# Cutman-RevB.net
KiCad netlist of a schematic drawn in EAGLE
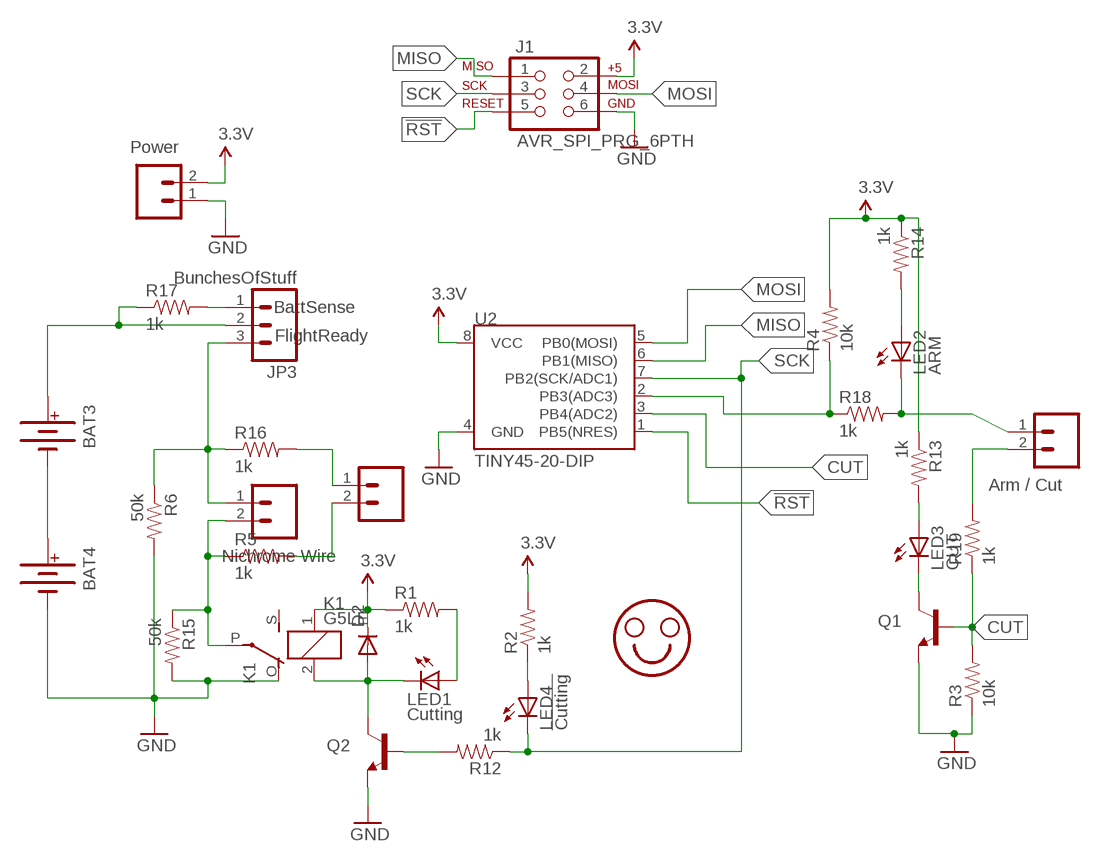
[diagram p0: schematic, sheet 1]

(export (version "E")
  (design (tool "Eeschema 10.0.6"))
  (components
    (comp (ref "BAT3")
      (value "BATTERYAA-KIT")
      (footprint "eagle-import:BATTERY-AA-KIT")
      (libsource (lib "eagle-import") (part "BATTERYAA-KIT"))
    )
    (comp (ref "BAT4")
      (value "BATTERYAA-KIT")
      (footprint "eagle-import:BATTERY-AA-KIT")
      (libsource (lib "eagle-import") (part "BATTERYAA-KIT"))
    )
    (comp (ref "D2")
      (value "DIODEPTH")
      (footprint "eagle-import:DIODE-1N4001")
      (libsource (lib "eagle-import") (part "DIODEPTH"))
    )
    (comp (ref "J1")
      (value "AVR_SPI_PRG_6PTH")
      (footprint "eagle-import:2X3")
      (libsource (lib "eagle-import") (part "AVR_SPI_PRG_6PTH"))
    )
    (comp (ref "JP1")
      (value "NichromeWire")
      (footprint "eagle-import:SCREWTERMINAL-3.5MM-2_LOCK")
      (libsource (lib "eagle-import") (part "M023.5MM_LOCK"))
    )
    (comp (ref "JP2")
      (value "Power")
      (footprint "eagle-import:SCREWTERMINAL-3.5MM-2_LOCK")
      (libsource (lib "eagle-import") (part "M023.5MM_LOCK"))
    )
    (comp (ref "JP3")
      (value "BunchesOfStuff")
      (footprint "eagle-import:SCREWTERMINAL-3.5MM-3")
      (libsource (lib "eagle-import") (part "M03SCREW"))
    )
    (comp (ref "JP4")
      (value "VSense")
      (footprint "eagle-import:SCREWTERMINAL-3.5MM-2_LOCK")
      (libsource (lib "eagle-import") (part "M023.5MM_LOCK"))
    )
    (comp (ref "JP6")
      (value "Arm/Cut")
      (footprint "eagle-import:SCREWTERMINAL-3.5MM-2_LOCK")
      (libsource (lib "eagle-import") (part "M023.5MM_LOCK"))
    )
    (comp (ref "K1")
      (value "G5LE")
      (footprint "eagle-import:G5LE")
      (libsource (lib "eagle-import") (part "G5LE"))
    )
    (comp (ref "LED1")
      (value "Cutting")
      (footprint "eagle-import:LED5MM")
      (libsource (lib "eagle-import") (part "LED5MM"))
    )
    (comp (ref "LED2")
      (value "ARM")
      (footprint "eagle-import:LED5MM")
      (libsource (lib "eagle-import") (part "LED5MM"))
    )
    (comp (ref "LED3")
      (value "CUT")
      (footprint "eagle-import:LED5MM")
      (libsource (lib "eagle-import") (part "LED5MM"))
    )
    (comp (ref "LED4")
      (value "!Cutting")
      (footprint "eagle-import:LED5MM")
      (libsource (lib "eagle-import") (part "LED5MM"))
    )
    (comp (ref "Q1")
      (value "TRANSISTOR_NPNTO92")
      (footprint "eagle-import:TO-92")
      (libsource (lib "eagle-import") (part "TRANSISTOR_NPNTO92"))
    )
    (comp (ref "Q2")
      (value "TRANSISTOR_NPNTO92")
      (footprint "eagle-import:TO-92")
      (libsource (lib "eagle-import") (part "TRANSISTOR_NPNTO92"))
    )
    (comp (ref "R1")
      (value "1k")
      (footprint "eagle-import:AXIAL-0.3")
      (libsource (lib "eagle-import") (part "RESISTORAXIAL-0.3"))
    )
    (comp (ref "R2")
      (value "1k")
      (footprint "eagle-import:AXIAL-0.3")
      (libsource (lib "eagle-import") (part "RESISTORAXIAL-0.3"))
    )
    (comp (ref "R3")
      (value "10k")
      (footprint "eagle-import:AXIAL-0.3")
      (libsource (lib "eagle-import") (part "RESISTORAXIAL-0.3"))
    )
    (comp (ref "R4")
      (value "10k")
      (footprint "eagle-import:AXIAL-0.3")
      (libsource (lib "eagle-import") (part "RESISTORAXIAL-0.3"))
    )
    (comp (ref "R5")
      (value "1k")
      (footprint "eagle-import:AXIAL-0.3")
      (libsource (lib "eagle-import") (part "RESISTORAXIAL-0.3"))
    )
    (comp (ref "R6")
      (value "50k")
      (footprint "eagle-import:AXIAL-0.3")
      (libsource (lib "eagle-import") (part "RESISTORAXIAL-0.3"))
    )
    (comp (ref "R12")
      (value "1k")
      (footprint "eagle-import:AXIAL-0.3")
      (libsource (lib "eagle-import") (part "RESISTORAXIAL-0.3"))
    )
    (comp (ref "R13")
      (value "1k")
      (footprint "eagle-import:AXIAL-0.3")
      (libsource (lib "eagle-import") (part "RESISTORAXIAL-0.3"))
    )
    (comp (ref "R14")
      (value "1k")
      (footprint "eagle-import:AXIAL-0.3")
      (libsource (lib "eagle-import") (part "RESISTORAXIAL-0.3"))
    )
    (comp (ref "R15")
      (value "50k")
      (footprint "eagle-import:AXIAL-0.3")
      (libsource (lib "eagle-import") (part "RESISTORAXIAL-0.3"))
    )
    (comp (ref "R16")
      (value "1k")
      (footprint "eagle-import:AXIAL-0.3")
      (libsource (lib "eagle-import") (part "RESISTORAXIAL-0.3"))
    )
    (comp (ref "R17")
      (value "1k")
      (footprint "eagle-import:AXIAL-0.3")
      (libsource (lib "eagle-import") (part "RESISTORAXIAL-0.3"))
    )
    (comp (ref "R18")
      (value "1k")
      (footprint "eagle-import:AXIAL-0.3")
      (libsource (lib "eagle-import") (part "RESISTORAXIAL-0.3"))
    )
    (comp (ref "R19")
      (value "1k")
      (footprint "eagle-import:AXIAL-0.3")
      (libsource (lib "eagle-import") (part "RESISTORAXIAL-0.3"))
    )
    (comp (ref "STANDOFF2")
      (value "STAND-OFF")
      (footprint "eagle-import:STAND-OFF")
      (libsource (lib "eagle-import") (part "STAND-OFF"))
    )
    (comp (ref "STANDOFF3")
      (value "STAND-OFF")
      (footprint "eagle-import:STAND-OFF")
      (libsource (lib "eagle-import") (part "STAND-OFF"))
    )
    (comp (ref "U2")
      (value "TINY45-20-DIP")
      (footprint "eagle-import:DIP08")
      (libsource (lib "eagle-import") (part "ATTINY45TINY45-20-DIP"))
    )
  )
  (nets
    (net (code "1") (name "/~{RST}") (class "Default")
      (node (ref "J1") (pin "5") (pinfunction "5_5") (pintype "passive"))
      (node (ref "U2") (pin "1") (pinfunction "PB5(NRES)_1") (pintype "bidirectional"))
    )
    (net (code "2") (name "3.3V") (class "Default")
      (node (ref "D2") (pin "C") (pinfunction "C_C") (pintype "passive"))
      (node (ref "J1") (pin "2") (pinfunction "2_2") (pintype "passive"))
      (node (ref "JP2") (pin "2") (pinfunction "2_2") (pintype "passive"))
      (node (ref "K1") (pin "1") (pinfunction "1_1") (pintype "passive"))
      (node (ref "R1") (pin "P$1") (pinfunction "1_P$1") (pintype "passive"))
      (node (ref "R13") (pin "P$1") (pinfunction "1_P$1") (pintype "passive"))
      (node (ref "R14") (pin "P$1") (pinfunction "1_P$1") (pintype "passive"))
      (node (ref "R2") (pin "P$2") (pinfunction "2_P$2") (pintype "passive"))
      (node (ref "R4") (pin "P$2") (pinfunction "2_P$2") (pintype "passive"))
      (node (ref "U2") (pin "8") (pinfunction "VCC_8") (pintype "bidirectional"))
    )
    (net (code "3") (name "CUT") (class "Default")
      (node (ref "Q1") (pin "2") (pinfunction "B_2") (pintype "passive"))
      (node (ref "R19") (pin "P$1") (pinfunction "1_P$1") (pintype "passive"))
      (node (ref "R3") (pin "P$2") (pinfunction "2_P$2") (pintype "passive"))
      (node (ref "U2") (pin "3") (pinfunction "PB4(ADC2)_3") (pintype "bidirectional"))
    )
    (net (code "4") (name "GND") (class "Default")
      (node (ref "BAT4") (pin "GND@1") (pinfunction "-_GND@1") (pintype "power_in"))
      (node (ref "BAT4") (pin "GND@2") (pinfunction "-_GND@2") (pintype "power_in"))
      (node (ref "J1") (pin "6") (pinfunction "6_6") (pintype "passive"))
      (node (ref "JP2") (pin "1") (pinfunction "1_1") (pintype "passive"))
      (node (ref "K1") (pin "O") (pinfunction "O_O") (pintype "passive"))
      (node (ref "Q1") (pin "1") (pinfunction "E_1") (pintype "passive"))
      (node (ref "Q2") (pin "1") (pinfunction "E_1") (pintype "passive"))
      (node (ref "R15") (pin "P$2") (pinfunction "2_P$2") (pintype "passive"))
      (node (ref "R3") (pin "P$1") (pinfunction "1_P$1") (pintype "passive"))
      (node (ref "R6") (pin "P$2") (pinfunction "2_P$2") (pintype "passive"))
      (node (ref "U2") (pin "4") (pinfunction "GND_4") (pintype "bidirectional"))
    )
    (net (code "5") (name "MISO") (class "Default")
      (node (ref "J1") (pin "1") (pinfunction "1_1") (pintype "passive"))
      (node (ref "U2") (pin "6") (pinfunction "PB1(MISO)_6") (pintype "bidirectional"))
    )
    (net (code "6") (name "MOSI") (class "Default")
      (node (ref "J1") (pin "4") (pinfunction "4_4") (pintype "passive"))
      (node (ref "U2") (pin "5") (pinfunction "PB0(MOSI)_5") (pintype "bidirectional"))
    )
    (net (code "7") (name "Net-(BAT3---PadGND@1)") (class "Default")
      (node (ref "BAT3") (pin "GND@1") (pinfunction "-_GND@1") (pintype "power_in"))
      (node (ref "BAT3") (pin "GND@2") (pinfunction "-_GND@2") (pintype "power_in"))
      (node (ref "BAT4") (pin "PWR@1") (pinfunction "+_PWR@1") (pintype "power_in"))
      (node (ref "BAT4") (pin "PWR@2") (pinfunction "+_PWR@2") (pintype "power_in"))
    )
    (net (code "8") (name "Net-(LED1-C)") (class "Default")
      (node (ref "D2") (pin "A") (pinfunction "A_A") (pintype "passive"))
      (node (ref "K1") (pin "2") (pinfunction "2_2") (pintype "passive"))
      (node (ref "LED1") (pin "K") (pinfunction "C_K") (pintype "passive"))
      (node (ref "Q2") (pin "3") (pinfunction "C_3") (pintype "passive"))
    )
    (net (code "9") (name "Net-(LED2-C)") (class "Default")
      (node (ref "JP6") (pin "1") (pinfunction "1_1") (pintype "passive"))
      (node (ref "LED2") (pin "K") (pinfunction "C_K") (pintype "passive"))
      (node (ref "R18") (pin "P$2") (pinfunction "2_P$2") (pintype "passive"))
    )
    (net (code "10") (name "Net-(LED3-C)") (class "Default")
      (node (ref "LED3") (pin "K") (pinfunction "C_K") (pintype "passive"))
      (node (ref "Q1") (pin "3") (pinfunction "C_3") (pintype "passive"))
    )
    (net (code "11") (name "Net-(Q2-B)") (class "Default")
      (node (ref "Q2") (pin "2") (pinfunction "B_2") (pintype "passive"))
      (node (ref "R12") (pin "P$2") (pinfunction "2_P$2") (pintype "passive"))
    )
    (net (code "12") (name "Net-(R1-2)") (class "Default")
      (node (ref "LED1") (pin "A") (pinfunction "A_A") (pintype "passive"))
      (node (ref "R1") (pin "P$2") (pinfunction "2_P$2") (pintype "passive"))
    )
    (net (code "13") (name "Net-(R2-1)") (class "Default")
      (node (ref "LED4") (pin "A") (pinfunction "A_A") (pintype "passive"))
      (node (ref "R2") (pin "P$1") (pinfunction "1_P$1") (pintype "passive"))
    )
    (net (code "14") (name "Net-(R5-2)") (class "Default")
      (node (ref "JP4") (pin "2") (pinfunction "2_2") (pintype "passive"))
      (node (ref "R5") (pin "P$2") (pinfunction "2_P$2") (pintype "passive"))
    )
    (net (code "15") (name "Net-(R13-2)") (class "Default")
      (node (ref "LED3") (pin "A") (pinfunction "A_A") (pintype "passive"))
      (node (ref "R13") (pin "P$2") (pinfunction "2_P$2") (pintype "passive"))
    )
    (net (code "16") (name "Net-(R14-2)") (class "Default")
      (node (ref "LED2") (pin "A") (pinfunction "A_A") (pintype "passive"))
      (node (ref "R14") (pin "P$2") (pinfunction "2_P$2") (pintype "passive"))
    )
    (net (code "17") (name "Net-(R15-1)") (class "Default")
      (node (ref "JP1") (pin "2") (pinfunction "2_2") (pintype "passive"))
      (node (ref "K1") (pin "P") (pinfunction "P_P") (pintype "passive"))
      (node (ref "R15") (pin "P$1") (pinfunction "1_P$1") (pintype "passive"))
      (node (ref "R5") (pin "P$1") (pinfunction "1_P$1") (pintype "passive"))
    )
    (net (code "18") (name "Net-(R16-1)") (class "Default")
      (node (ref "JP1") (pin "1") (pinfunction "1_1") (pintype "passive"))
      (node (ref "JP3") (pin "3") (pinfunction "3_3") (pintype "passive"))
      (node (ref "R16") (pin "P$1") (pinfunction "1_P$1") (pintype "passive"))
      (node (ref "R6") (pin "P$1") (pinfunction "1_P$1") (pintype "passive"))
    )
    (net (code "19") (name "Net-(R16-2)") (class "Default")
      (node (ref "JP4") (pin "1") (pinfunction "1_1") (pintype "passive"))
      (node (ref "R16") (pin "P$2") (pinfunction "2_P$2") (pintype "passive"))
    )
    (net (code "20") (name "Net-(R17-1)") (class "Default")
      (node (ref "BAT3") (pin "PWR@1") (pinfunction "+_PWR@1") (pintype "power_in"))
      (node (ref "BAT3") (pin "PWR@2") (pinfunction "+_PWR@2") (pintype "power_in"))
      (node (ref "JP3") (pin "2") (pinfunction "2_2") (pintype "passive"))
      (node (ref "R17") (pin "P$1") (pinfunction "1_P$1") (pintype "passive"))
    )
    (net (code "21") (name "Net-(R17-2)") (class "Default")
      (node (ref "JP3") (pin "1") (pinfunction "1_1") (pintype "passive"))
      (node (ref "R17") (pin "P$2") (pinfunction "2_P$2") (pintype "passive"))
    )
    (net (code "22") (name "Net-(R18-1)") (class "Default")
      (node (ref "R18") (pin "P$1") (pinfunction "1_P$1") (pintype "passive"))
      (node (ref "R4") (pin "P$1") (pinfunction "1_P$1") (pintype "passive"))
      (node (ref "U2") (pin "2") (pinfunction "PB3(ADC3)_2") (pintype "bidirectional"))
    )
    (net (code "23") (name "Net-(R19-2)") (class "Default")
      (node (ref "JP6") (pin "2") (pinfunction "2_2") (pintype "passive"))
      (node (ref "R19") (pin "P$2") (pinfunction "2_P$2") (pintype "passive"))
    )
    (net (code "24") (name "SCK") (class "Default")
      (node (ref "J1") (pin "3") (pinfunction "3_3") (pintype "passive"))
      (node (ref "LED4") (pin "K") (pinfunction "C_K") (pintype "passive"))
      (node (ref "R12") (pin "P$1") (pinfunction "1_P$1") (pintype "passive"))
      (node (ref "U2") (pin "7") (pinfunction "PB2(SCK/ADC1)_7") (pintype "bidirectional"))
    )
    (net (code "25") (name "unconnected-(K1-PadS)") (class "Default")
      (node (ref "K1") (pin "S") (pinfunction "S_S") (pintype "passive"))
    )
  )
)
